# ESP32.net
KiCad netlist of a schematic drawn in Altium Designer
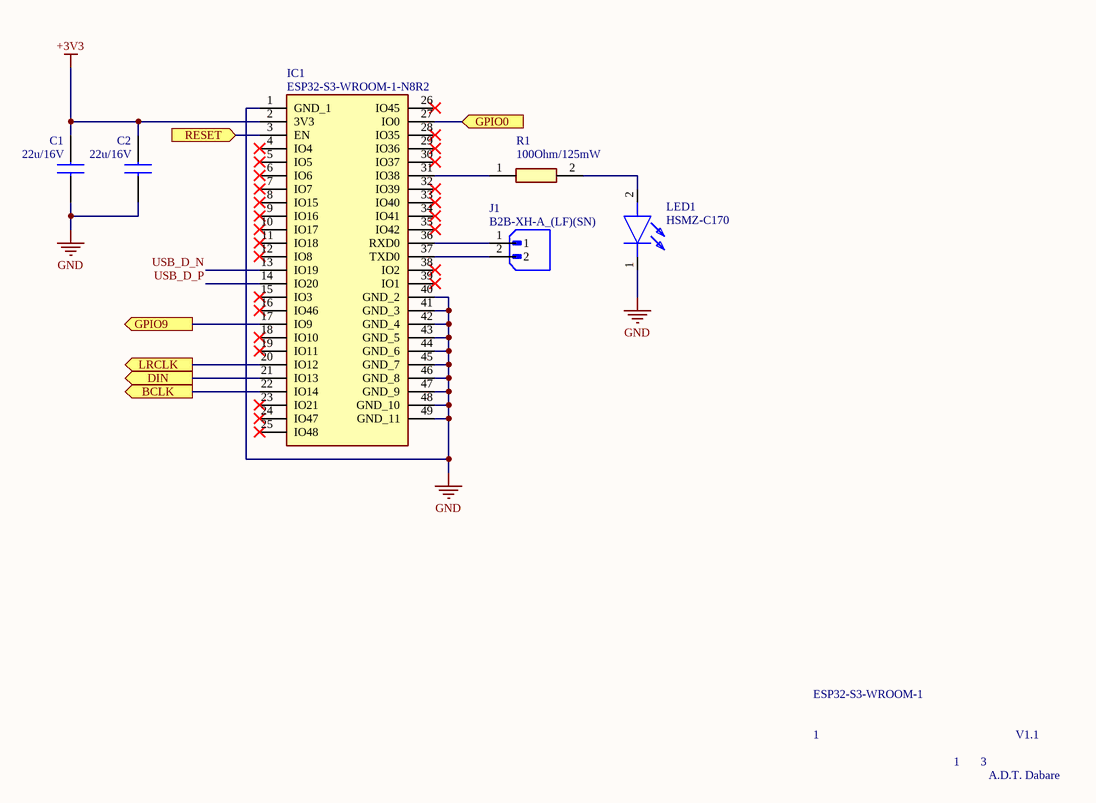
[diagram p0: ESP32.SchDoc]

(export (version "E")
  (design (tool "Eeschema 10.0.6"))
  (components
    (comp (ref "C1")
      (value "22u/16V")
      (footprint "SamacSys:CAPC2012X94N")
      (fields
        (field (name "MANUFACTURER_PART_NUMBER") "0805YC106KAT2A")
        (field (name "MOUSER PART NUMBER") "581-0805YC106KAT2A")
      )
      (libsource (lib "*") (part "0805YC106KAT2A"))
    )
    (comp (ref "C2")
      (value "22u/16V")
      (footprint "SamacSys:C0805")
      (description "Multilayer Ceramic Capacitors MLCC - SMD/SMT 16V 0.1uF X7R 0805 10% Flex AEC-Q200")
      (fields
        (field (name "MANUFACTURER_PART_NUMBER") "C0805X104K4RACAUTO")
        (field (name "MOUSER PART NUMBER") "80-C0805X104K4RAUTO")
      )
      (libsource (lib "*") (part "C0805X104K4RACAUTO"))
    )
    (comp (ref "IC1")
      (value "ESP32-S3-WROOM-1-N8R2")
      (footprint "SamacSys:ESP32S3WROOM1N8R2")
      (description "Integrated Circuit")
      (fields (field (name "MOUSER PART NUMBER") "356-ESP32-S3WRM1N8R2"))
      (libsource (lib "*") (part "ESP32-S3-WROOM-1-N8R2"))
    )
    (comp (ref "J1")
      (value "B2B-XH-A_(LF)(SN)")
      (footprint "JST_B2B-XH-A_(LF)(SN)")
      (description "Connector Header Through Hole 2 position 0.098 (2.50mm)")
      (fields (field (name "MF") "JST Sales") (field (name "MP") "B2B-XH-A (LF)(SN)"))
      (libsource (lib "B2B-XH-A__LF__SN_") (part "B2B-XH-A_(LF)(SN)"))
    )
    (comp (ref "LED1")
      (value "HSMZ-C170")
      (footprint "SamacSys:LEDC2012X90N")
      (description "Standard LEDs - SMD AlInGaP2 Red 2 Red")
      (fields (field (name "MOUSER PART NUMBER") "630-HSMZ-C170"))
      (libsource (lib "*") (part "HSMZ-C170"))
    )
    (comp (ref "R1")
      (value "100Ohm/125mW")
      (footprint "SamacSys:ERA6AEB101V")
      (description "Thin Film Resistors - SMD 0805 56ohms 25ppm 0.5% AEC-Q200")
      (fields (field (name "MANUFACTURER_PART_NUMBER") "ERA-6AED560V"))
      (libsource (lib "*") (part "ERA-6AED560V"))
    )
  )
  (nets
    (net (code "1") (name "+3V3") (class "Default")
      (node (ref "C1") (pin "1") (pinfunction "1_1") (pintype "passive"))
      (node (ref "C2") (pin "1") (pinfunction "1_1") (pintype "passive"))
      (node (ref "IC1") (pin "2") (pinfunction "3V3_2") (pintype "passive"))
    )
    (net (code "2") (name "/BCLK") (class "Default")
      (node (ref "IC1") (pin "22") (pinfunction "IO14_22") (pintype "passive"))
    )
    (net (code "3") (name "/DIN") (class "Default")
      (node (ref "IC1") (pin "21") (pinfunction "IO13_21") (pintype "passive"))
    )
    (net (code "4") (name "/GPIO0") (class "Default")
      (node (ref "IC1") (pin "27") (pinfunction "IO0_27") (pintype "passive"))
    )
    (net (code "5") (name "/GPIO9") (class "Default")
      (node (ref "IC1") (pin "17") (pinfunction "IO9_17") (pintype "passive"))
    )
    (net (code "6") (name "/LRCLK") (class "Default")
      (node (ref "IC1") (pin "20") (pinfunction "IO12_20") (pintype "passive"))
    )
    (net (code "7") (name "/RESET") (class "Default")
      (node (ref "IC1") (pin "3") (pinfunction "EN_3") (pintype "passive"))
    )
    (net (code "8") (name "/USB_D_N") (class "Default")
      (node (ref "IC1") (pin "13") (pinfunction "IO19_13") (pintype "passive"))
    )
    (net (code "9") (name "/USB_D_P") (class "Default")
      (node (ref "IC1") (pin "14") (pinfunction "IO20_14") (pintype "passive"))
    )
    (net (code "10") (name "GND") (class "Default")
      (node (ref "C1") (pin "2") (pinfunction "2_2") (pintype "passive"))
      (node (ref "C2") (pin "2") (pinfunction "2_2") (pintype "passive"))
      (node (ref "IC1") (pin "1") (pinfunction "GND_1_1") (pintype "passive"))
      (node (ref "IC1") (pin "40") (pinfunction "GND_2_40") (pintype "passive"))
      (node (ref "IC1") (pin "41") (pinfunction "GND_3_41") (pintype "passive"))
      (node (ref "IC1") (pin "42") (pinfunction "GND_4_42") (pintype "passive"))
      (node (ref "IC1") (pin "43") (pinfunction "GND_5_43") (pintype "passive"))
      (node (ref "IC1") (pin "44") (pinfunction "GND_6_44") (pintype "passive"))
      (node (ref "IC1") (pin "45") (pinfunction "GND_7_45") (pintype "passive"))
      (node (ref "IC1") (pin "46") (pinfunction "GND_8_46") (pintype "passive"))
      (node (ref "IC1") (pin "47") (pinfunction "GND_9_47") (pintype "passive"))
      (node (ref "IC1") (pin "48") (pinfunction "GND_10_48") (pintype "passive"))
      (node (ref "IC1") (pin "49") (pinfunction "GND_11_49") (pintype "passive"))
      (node (ref "LED1") (pin "1") (pinfunction "K_1") (pintype "passive"))
    )
    (net (code "11") (name "Net-(IC1-IO38)") (class "Default")
      (node (ref "IC1") (pin "31") (pinfunction "IO38_31") (pintype "passive"))
      (node (ref "R1") (pin "1") (pinfunction "1_1") (pintype "passive"))
    )
    (net (code "12") (name "Net-(IC1-RXD0)") (class "Default")
      (node (ref "IC1") (pin "36") (pinfunction "RXD0_36") (pintype "passive"))
      (node (ref "J1") (pin "1") (pinfunction "1_1") (pintype "passive"))
    )
    (net (code "13") (name "Net-(IC1-TXD0)") (class "Default")
      (node (ref "IC1") (pin "37") (pinfunction "TXD0_37") (pintype "passive"))
      (node (ref "J1") (pin "2") (pinfunction "2_2") (pintype "passive"))
    )
    (net (code "14") (name "Net-(LED1-A)") (class "Default")
      (node (ref "LED1") (pin "2") (pinfunction "A_2") (pintype "passive"))
      (node (ref "R1") (pin "2") (pinfunction "2_2") (pintype "passive"))
    )
    (net (code "15") (name "unconnected-(IC1-IO1-Pad39)") (class "Default")
      (node (ref "IC1") (pin "39") (pinfunction "IO1_39") (pintype "passive+no_connect"))
    )
    (net (code "16") (name "unconnected-(IC1-IO2-Pad38)") (class "Default")
      (node (ref "IC1") (pin "38") (pinfunction "IO2_38") (pintype "passive+no_connect"))
    )
    (net (code "17") (name "unconnected-(IC1-IO3-Pad15)") (class "Default")
      (node (ref "IC1") (pin "15") (pinfunction "IO3_15") (pintype "passive+no_connect"))
    )
    (net (code "18") (name "unconnected-(IC1-IO4-Pad4)") (class "Default")
      (node (ref "IC1") (pin "4") (pinfunction "IO4_4") (pintype "passive+no_connect"))
    )
    (net (code "19") (name "unconnected-(IC1-IO5-Pad5)") (class "Default")
      (node (ref "IC1") (pin "5") (pinfunction "IO5_5") (pintype "passive+no_connect"))
    )
    (net (code "20") (name "unconnected-(IC1-IO6-Pad6)") (class "Default")
      (node (ref "IC1") (pin "6") (pinfunction "IO6_6") (pintype "passive+no_connect"))
    )
    (net (code "21") (name "unconnected-(IC1-IO7-Pad7)") (class "Default")
      (node (ref "IC1") (pin "7") (pinfunction "IO7_7") (pintype "passive+no_connect"))
    )
    (net (code "22") (name "unconnected-(IC1-IO8-Pad12)") (class "Default")
      (node (ref "IC1") (pin "12") (pinfunction "IO8_12") (pintype "passive+no_connect"))
    )
    (net (code "23") (name "unconnected-(IC1-IO10-Pad18)") (class "Default")
      (node (ref "IC1") (pin "18") (pinfunction "IO10_18") (pintype "passive+no_connect"))
    )
    (net (code "24") (name "unconnected-(IC1-IO11-Pad19)") (class "Default")
      (node (ref "IC1") (pin "19") (pinfunction "IO11_19") (pintype "passive+no_connect"))
    )
    (net (code "25") (name "unconnected-(IC1-IO15-Pad8)") (class "Default")
      (node (ref "IC1") (pin "8") (pinfunction "IO15_8") (pintype "passive+no_connect"))
    )
    (net (code "26") (name "unconnected-(IC1-IO16-Pad9)") (class "Default")
      (node (ref "IC1") (pin "9") (pinfunction "IO16_9") (pintype "passive+no_connect"))
    )
    (net (code "27") (name "unconnected-(IC1-IO17-Pad10)") (class "Default")
      (node (ref "IC1") (pin "10") (pinfunction "IO17_10") (pintype "passive+no_connect"))
    )
    (net (code "28") (name "unconnected-(IC1-IO18-Pad11)") (class "Default")
      (node (ref "IC1") (pin "11") (pinfunction "IO18_11") (pintype "passive+no_connect"))
    )
    (net (code "29") (name "unconnected-(IC1-IO21-Pad23)") (class "Default")
      (node (ref "IC1") (pin "23") (pinfunction "IO21_23") (pintype "passive+no_connect"))
    )
    (net (code "30") (name "unconnected-(IC1-IO35-Pad28)") (class "Default")
      (node (ref "IC1") (pin "28") (pinfunction "IO35_28") (pintype "passive+no_connect"))
    )
    (net (code "31") (name "unconnected-(IC1-IO36-Pad29)") (class "Default")
      (node (ref "IC1") (pin "29") (pinfunction "IO36_29") (pintype "passive+no_connect"))
    )
    (net (code "32") (name "unconnected-(IC1-IO37-Pad30)") (class "Default")
      (node (ref "IC1") (pin "30") (pinfunction "IO37_30") (pintype "passive+no_connect"))
    )
    (net (code "33") (name "unconnected-(IC1-IO39-Pad32)") (class "Default")
      (node (ref "IC1") (pin "32") (pinfunction "IO39_32") (pintype "passive+no_connect"))
    )
    (net (code "34") (name "unconnected-(IC1-IO40-Pad33)") (class "Default")
      (node (ref "IC1") (pin "33") (pinfunction "IO40_33") (pintype "passive+no_connect"))
    )
    (net (code "35") (name "unconnected-(IC1-IO41-Pad34)") (class "Default")
      (node (ref "IC1") (pin "34") (pinfunction "IO41_34") (pintype "passive+no_connect"))
    )
    (net (code "36") (name "unconnected-(IC1-IO42-Pad35)") (class "Default")
      (node (ref "IC1") (pin "35") (pinfunction "IO42_35") (pintype "passive+no_connect"))
    )
    (net (code "37") (name "unconnected-(IC1-IO45-Pad26)") (class "Default")
      (node (ref "IC1") (pin "26") (pinfunction "IO45_26") (pintype "passive+no_connect"))
    )
    (net (code "38") (name "unconnected-(IC1-IO46-Pad16)") (class "Default")
      (node (ref "IC1") (pin "16") (pinfunction "IO46_16") (pintype "passive+no_connect"))
    )
    (net (code "39") (name "unconnected-(IC1-IO47-Pad24)") (class "Default")
      (node (ref "IC1") (pin "24") (pinfunction "IO47_24") (pintype "passive+no_connect"))
    )
    (net (code "40") (name "unconnected-(IC1-IO48-Pad25)") (class "Default")
      (node (ref "IC1") (pin "25") (pinfunction "IO48_25") (pintype "passive+no_connect"))
    )
  )
)
